# main.net
KiCad netlist of a schematic drawn in Altium Designer
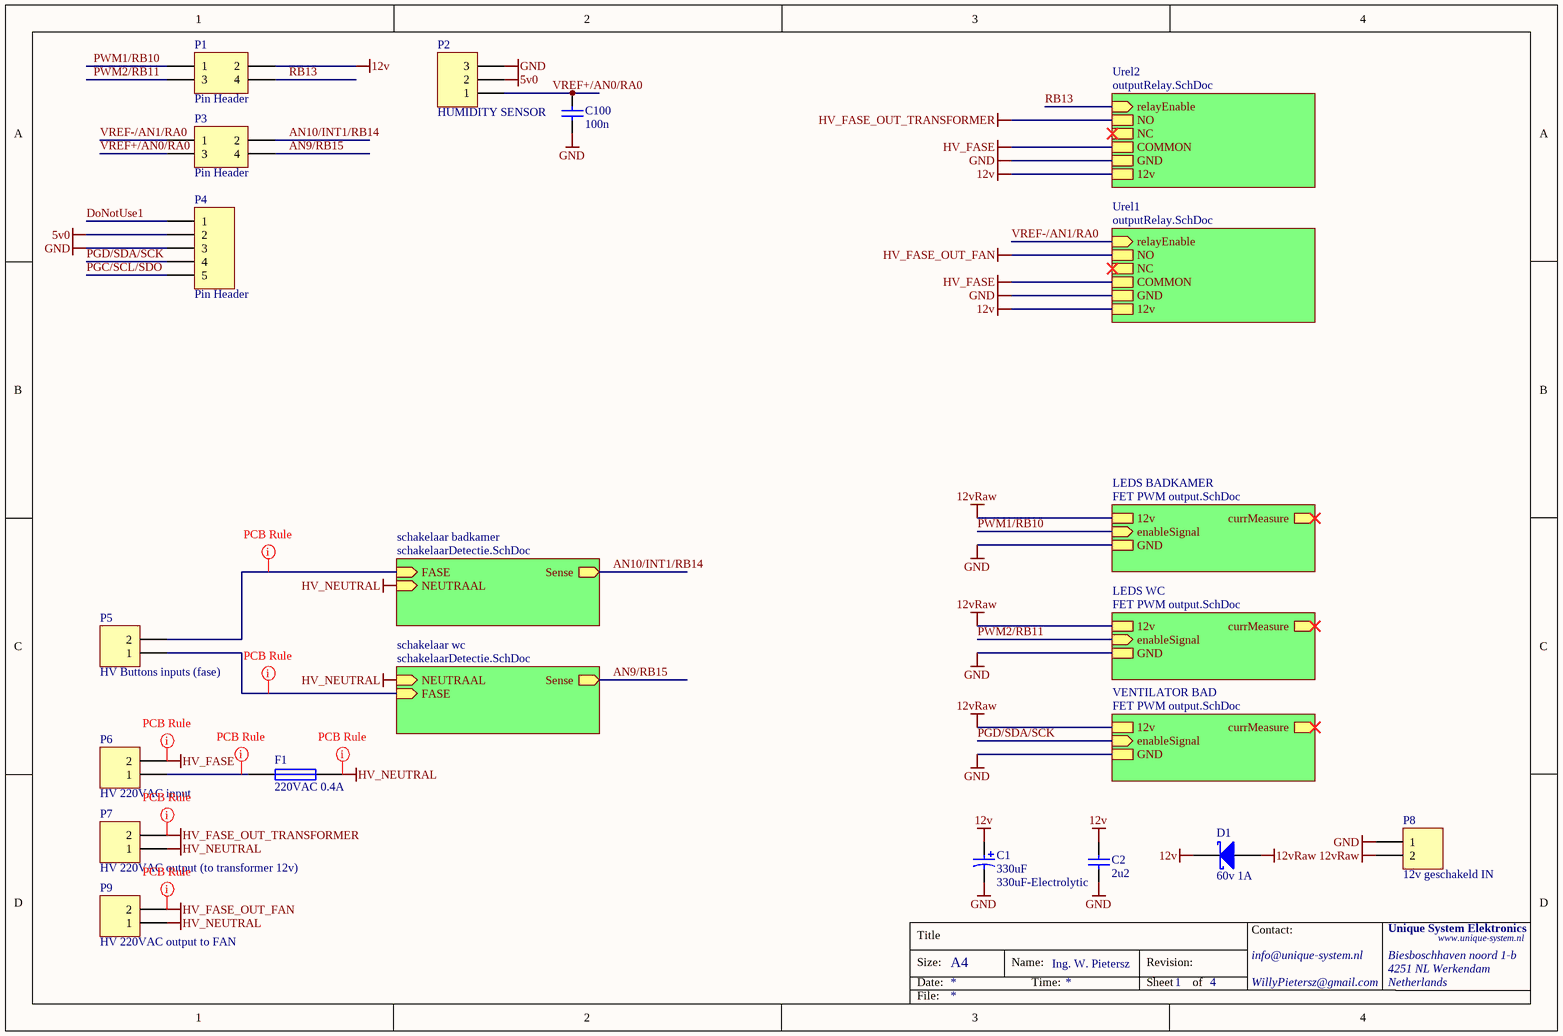
[diagram p0: main.SchDoc]

(export (version "E")
  (design (tool "Eeschema 10.0.6"))
  (components
    (comp (ref "C1")
      (value "330uF")
      (footprint "SMT CASE G")
      (description "Capacitor")
      (fields
        (field (name "PART NUMBER") "330uF-Electrolytic")
        (field (name "VOLTAGE") "35V")
        (field (name "TOLERANCE") "0.2")
        (field (name "AUTHOR") "Willem Pietersz")
      )
      (libsource (lib "OurDb") (part "cap_Polar"))
    )
    (comp (ref "C2")
      (value "2u2")
      (footprint "C0805")
      (fields
        (field (name "VOLTAGE") "50")
        (field (name "TOLERANCE") "0.1")
        (field (name "AUTHOR") "Willy Pietersz")
      )
      (libsource (lib "OurDb") (part "cap_NonPolar"))
    )
    (comp (ref "C100")
      (value "100n")
      (footprint "C0805")
      (fields
        (field (name "VOLTAGE") "50v")
        (field (name "TOLERANCE") "0.1")
        (field (name "AUTHOR") "Willy Pietersz")
      )
      (libsource (lib "OurDb") (part "cap_NonPolar"))
    )
    (comp (ref "D1")
      (value "60v 1A")
      (footprint "SOD323")
      (fields
        (field (name "PART NUMBER") "PMEG6010CEJ")
        (field (name "VOLTAGE") "60V")
        (field (name "AUTHOR") "Willem Pietersz")
      )
      (libsource (lib "OurDb") (part "SCHOTTKY"))
    )
    (comp (ref "F1")
      (value "220VAC 0.4A")
      (footprint "Rachem_R8")
      (description "Fuse")
      (fields
        (field (name "PART NUMBER") "LVR040K")
        (field (name "VOLTAGE") "220VAC")
        (field (name "PUBLISHER") "Altium Limited")
      )
      (libsource (lib "OurDb") (part "Fuse 1"))
    )
    (comp (ref "P1")
      (value "Pin Header")
      (footprint "HDR2X2-SMT-1.27")
      (description "Header, 2-Pin, Dual row")
      (fields (field (name "PART NUMBER") "PH2x2-SMT-1.27"))
      (libsource (lib "OurDb") (part "Con2x2"))
    )
    (comp (ref "P2")
      (value "HUMIDITY SENSOR")
      (footprint "TB3_3.5")
      (description "Con1x3")
      (fields
        (field (name "PART NUMBER") "TB3")
        (field (name "VOLTAGE") "300")
        (field (name "AUTHOR") "Willy Pietersz")
      )
      (libsource (lib "OurDb") (part "Con1x3"))
    )
    (comp (ref "P3")
      (value "Pin Header")
      (footprint "HDR2X2-SMT-1.27")
      (description "Header, 2-Pin, Dual row")
      (fields (field (name "PART NUMBER") "PH2x2-SMT-1.27"))
      (libsource (lib "OurDb") (part "Con2x2"))
    )
    (comp (ref "P4")
      (value "Pin Header")
      (footprint "HDR1X5 SMT")
      (description "Con1x5")
      (fields (field (name "PART NUMBER") "PH1x5 SMT"))
      (libsource (lib "OurDb") (part "Con1x5"))
    )
    (comp (ref "P5")
      (value "HV Buttons inputs (fase)")
      (footprint "TB2_5.08")
      (description "Con1x2")
      (fields
        (field (name "PART NUMBER") "TB2")
        (field (name "VOLTAGE") "300")
        (field (name "AUTHOR") "Bram van Rensen")
      )
      (libsource (lib "OurDb") (part "Con1x2"))
    )
    (comp (ref "P6")
      (value "HV 220VAC input")
      (footprint "TB2_5.08")
      (description "Con1x2")
      (fields
        (field (name "PART NUMBER") "TB2")
        (field (name "VOLTAGE") "300")
        (field (name "AUTHOR") "Bram van Rensen")
      )
      (libsource (lib "OurDb") (part "Con1x2"))
    )
    (comp (ref "P7")
      (value "HV 220VAC output (to transformer 12v)")
      (footprint "TB2_5.08")
      (description "Con1x2")
      (fields
        (field (name "PART NUMBER") "TB2")
        (field (name "VOLTAGE") "300")
        (field (name "AUTHOR") "Bram van Rensen")
      )
      (libsource (lib "OurDb") (part "Con1x2"))
    )
    (comp (ref "P8")
      (value "12v geschakeld IN")
      (footprint "TB2_5.08")
      (description "Con1x2")
      (fields
        (field (name "PART NUMBER") "TB2")
        (field (name "VOLTAGE") "300")
        (field (name "AUTHOR") "Bram van Rensen")
      )
      (libsource (lib "") (part "Con1x2_1"))
    )
    (comp (ref "P9")
      (value "HV 220VAC output to FAN")
      (footprint "TB2_5.08")
      (description "Con1x2")
      (fields
        (field (name "PART NUMBER") "TB2")
        (field (name "VOLTAGE") "300")
        (field (name "AUTHOR") "Bram van Rensen")
      )
      (libsource (lib "OurDb") (part "Con1x2"))
    )
  )
  (nets
    (net (code "1") (name "/AN9{slash}RB15") (class "Default")
      (node (ref "P3") (pin "4") (pinfunction "4_4") (pintype "passive"))
    )
    (net (code "2") (name "/AN10{slash}INT1{slash}RB14") (class "Default")
      (node (ref "P3") (pin "2") (pinfunction "2_2") (pintype "passive"))
    )
    (net (code "3") (name "/DoNotUse1") (class "Default")
      (node (ref "P4") (pin "1") (pinfunction "1_1") (pintype "passive"))
    )
    (net (code "4") (name "/FASE") (class "Default")
      (node (ref "P5") (pin "1") (pinfunction "1_1") (pintype "passive"))
    )
    (net (code "5") (name "/FASE_1") (class "Default")
      (node (ref "P5") (pin "2") (pinfunction "2_2") (pintype "passive"))
    )
    (net (code "8") (name "/PGC{slash}SCL{slash}SDO") (class "Default")
      (node (ref "P4") (pin "5") (pinfunction "5_5") (pintype "passive"))
    )
    (net (code "9") (name "/PGD{slash}SDA{slash}SCK") (class "Default")
      (node (ref "P4") (pin "4") (pinfunction "4_4") (pintype "passive"))
    )
    (net (code "10") (name "/PWM1{slash}RB10") (class "Default")
      (node (ref "P1") (pin "1") (pinfunction "1_1") (pintype "passive"))
    )
    (net (code "11") (name "/PWM2{slash}RB11") (class "Default")
      (node (ref "P1") (pin "3") (pinfunction "3_3") (pintype "passive"))
    )
    (net (code "12") (name "/RB13") (class "Default")
      (node (ref "P1") (pin "4") (pinfunction "4_4") (pintype "passive"))
    )
    (net (code "13") (name "/VREF+{slash}AN0{slash}RA0") (class "Default")
      (node (ref "C100") (pin "2") (pinfunction "2_2") (pintype "passive"))
      (node (ref "P2") (pin "1") (pinfunction "1_1") (pintype "passive"))
      (node (ref "P3") (pin "3") (pinfunction "3_3") (pintype "passive"))
    )
    (net (code "14") (name "/VREF-{slash}AN1{slash}RA0") (class "Default")
      (node (ref "P3") (pin "1") (pinfunction "1_1") (pintype "passive"))
    )
    (net (code "18") (name "5v0") (class "Default")
      (node (ref "P2") (pin "2") (pinfunction "2_2") (pintype "passive"))
      (node (ref "P4") (pin "2") (pinfunction "2_2") (pintype "passive"))
    )
    (net (code "19") (name "12v") (class "Default")
      (node (ref "C1") (pin "2") (pinfunction "2_2") (pintype "passive"))
      (node (ref "C2") (pin "2") (pinfunction "2_2") (pintype "passive"))
      (node (ref "D1") (pin "2") (pinfunction "2_2") (pintype "passive"))
      (node (ref "P1") (pin "2") (pinfunction "2_2") (pintype "passive"))
    )
    (net (code "20") (name "12vRaw") (class "Default")
      (node (ref "D1") (pin "1") (pinfunction "1_1") (pintype "passive"))
      (node (ref "P8") (pin "2") (pinfunction "2_2") (pintype "passive"))
    )
    (net (code "21") (name "GND") (class "Default")
      (node (ref "C1") (pin "1") (pinfunction "1_1") (pintype "passive"))
      (node (ref "C100") (pin "1") (pinfunction "1_1") (pintype "passive"))
      (node (ref "C2") (pin "1") (pinfunction "1_1") (pintype "passive"))
      (node (ref "P2") (pin "3") (pinfunction "3_3") (pintype "passive"))
      (node (ref "P4") (pin "3") (pinfunction "3_3") (pintype "passive"))
      (node (ref "P8") (pin "1") (pinfunction "1_1") (pintype "passive"))
    )
    (net (code "22") (name "HV_FASE") (class "Default")
      (node (ref "P6") (pin "2") (pinfunction "2_2") (pintype "passive"))
    )
    (net (code "23") (name "HV_FASE_OUT_FAN") (class "Default")
      (node (ref "P9") (pin "2") (pinfunction "2_2") (pintype "passive"))
    )
    (net (code "24") (name "HV_FASE_OUT_TRANSFORMER") (class "Default")
      (node (ref "P7") (pin "2") (pinfunction "2_2") (pintype "passive"))
    )
    (net (code "25") (name "HV_NEUTRAL") (class "Default")
      (node (ref "F1") (pin "1") (pinfunction "1_1") (pintype "passive"))
      (node (ref "P7") (pin "1") (pinfunction "1_1") (pintype "passive"))
      (node (ref "P9") (pin "1") (pinfunction "1_1") (pintype "passive"))
    )
    (net (code "26") (name "Net-(F1-Pad2)") (class "Default")
      (node (ref "F1") (pin "2") (pinfunction "2_2") (pintype "passive"))
      (node (ref "P6") (pin "1") (pinfunction "1_1") (pintype "passive"))
    )
  )
)
